# RoomSenosorV1.net
KiCad netlist of a schematic drawn in EAGLE
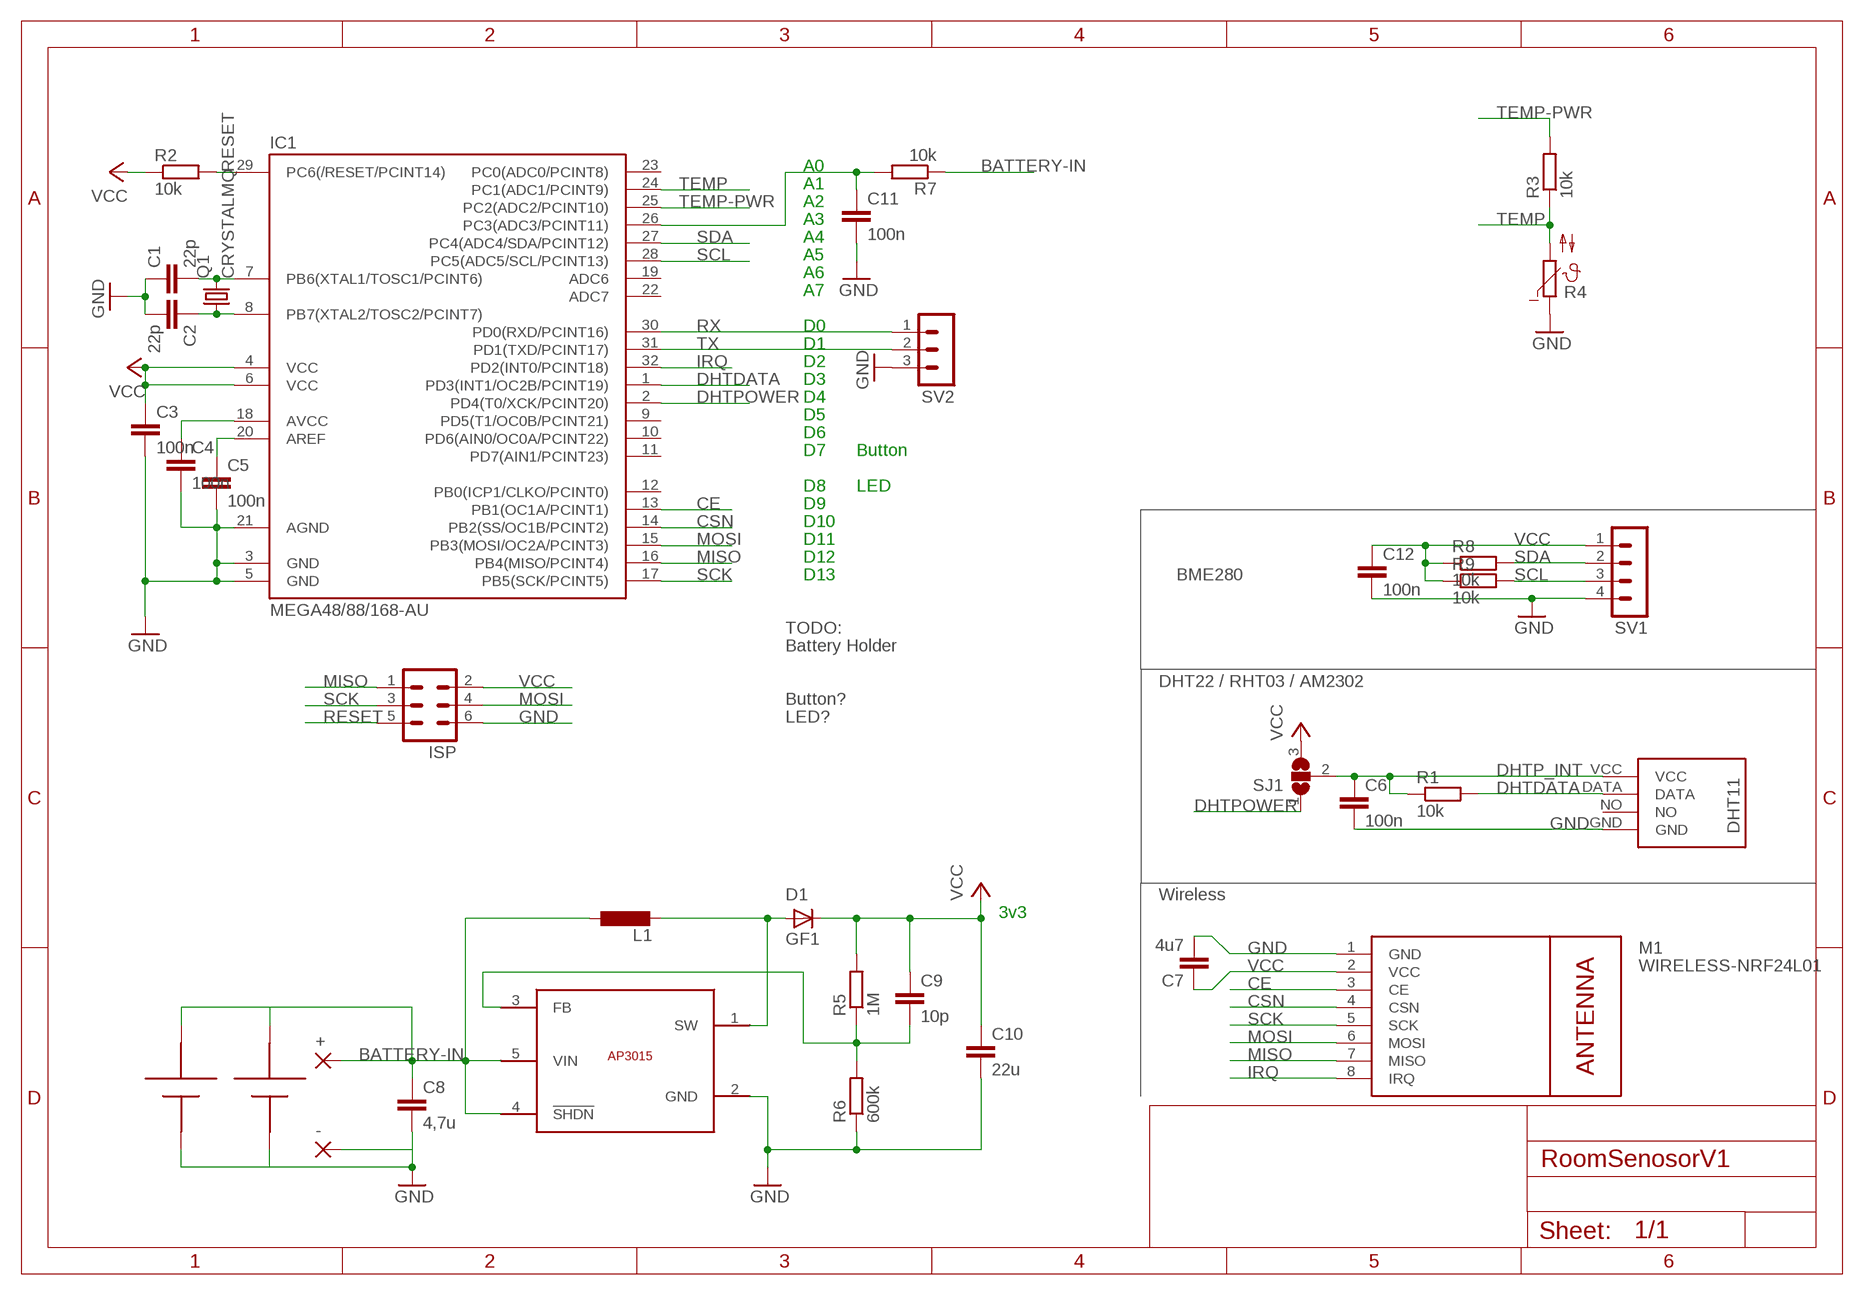
[diagram p0: schematic, sheet 1]

(export (version "E")
  (design (tool "Eeschema 10.0.6"))
  (components
    (comp (ref "+")
      (value "1,6/0,8")
      (footprint "eagle-import:1,6_0,8")
      (libsource (lib "eagle-import") (part "1,6/0,8"))
    )
    (comp (ref "-")
      (value "1,6/0,8")
      (footprint "eagle-import:1,6_0,8")
      (libsource (lib "eagle-import") (part "1,6/0,8"))
    )
    (comp (ref "C1")
      (value "22p")
      (footprint "eagle-import:C0805")
      (libsource (lib "eagle-import") (part "C-EUC0805"))
    )
    (comp (ref "C2")
      (value "22p")
      (footprint "eagle-import:C0805")
      (libsource (lib "eagle-import") (part "C-EUC0805"))
    )
    (comp (ref "C3")
      (value "100n")
      (footprint "eagle-import:C0805")
      (libsource (lib "eagle-import") (part "C-EUC0805"))
    )
    (comp (ref "C4")
      (value "100n")
      (footprint "eagle-import:C0805")
      (libsource (lib "eagle-import") (part "C-EUC0805"))
    )
    (comp (ref "C5")
      (value "100n")
      (footprint "eagle-import:C0805")
      (libsource (lib "eagle-import") (part "C-EUC0805"))
    )
    (comp (ref "C6")
      (value "100n")
      (footprint "eagle-import:C0805")
      (libsource (lib "eagle-import") (part "C-EUC0805"))
    )
    (comp (ref "C7")
      (value "4u7")
      (footprint "eagle-import:C0805")
      (libsource (lib "eagle-import") (part "C-EUC0805"))
    )
    (comp (ref "C8")
      (value "4,7u")
      (footprint "eagle-import:C0805")
      (libsource (lib "eagle-import") (part "C-EUC0805"))
    )
    (comp (ref "C9")
      (value "10p")
      (footprint "eagle-import:C0805")
      (libsource (lib "eagle-import") (part "C-EUC0805"))
    )
    (comp (ref "C10")
      (value "22u")
      (footprint "eagle-import:C1206")
      (libsource (lib "eagle-import") (part "C-EUC1206"))
    )
    (comp (ref "C11")
      (value "100n")
      (footprint "eagle-import:C0805")
      (libsource (lib "eagle-import") (part "C-EUC0805"))
    )
    (comp (ref "C12")
      (value "100n")
      (footprint "eagle-import:C0805")
      (libsource (lib "eagle-import") (part "C-EUC0805"))
    )
    (comp (ref "D1")
      (value "GF1")
      (footprint "eagle-import:SMA-DO214AC")
      (libsource (lib "eagle-import") (part "GF1"))
    )
    (comp (ref "IC1")
      (value "MEGA48/88/168-AU")
      (footprint "eagle-import:TQFP32-08")
      (libsource (lib "eagle-import") (part "MEGA48/88/168-AU"))
    )
    (comp (ref "ISP")
      (value "MA03-2")
      (footprint "eagle-import:MA03-2")
      (libsource (lib "eagle-import") (part "MA03-2"))
    )
    (comp (ref "L1")
      (value "L-EUL2825P")
      (footprint "eagle-import:L2825P")
      (libsource (lib "eagle-import") (part "L-EUL2825P"))
    )
    (comp (ref "M1")
      (value "WIRELESS-NRF24L01")
      (footprint "eagle-import:WIRELESS-NRF24L01")
      (libsource (lib "eagle-import") (part "WIRELESS-NRF24L01"))
    )
    (comp (ref "Q1")
      (value "CRYSTALMQ")
      (footprint "eagle-import:MQ")
      (libsource (lib "eagle-import") (part "CRYSTALMQ"))
    )
    (comp (ref "R1")
      (value "10k")
      (footprint "eagle-import:R0805")
      (libsource (lib "eagle-import") (part "R-EU_R0805"))
    )
    (comp (ref "R2")
      (value "10k")
      (footprint "eagle-import:R0805")
      (libsource (lib "eagle-import") (part "R-EU_R0805"))
    )
    (comp (ref "R3")
      (value "10k")
      (footprint "eagle-import:R0805")
      (libsource (lib "eagle-import") (part "R-EU_R0805"))
    )
    (comp (ref "R4")
      (value "NTC640")
      (footprint "eagle-import:P640")
      (libsource (lib "eagle-import") (part "NTC640"))
    )
    (comp (ref "R5")
      (value "1M")
      (footprint "eagle-import:R0805")
      (libsource (lib "eagle-import") (part "R-EU_R0805"))
    )
    (comp (ref "R6")
      (value "600k")
      (footprint "eagle-import:R0805")
      (libsource (lib "eagle-import") (part "R-EU_R0805"))
    )
    (comp (ref "R7")
      (value "10k")
      (footprint "eagle-import:R0805")
      (libsource (lib "eagle-import") (part "R-EU_R0805"))
    )
    (comp (ref "R8")
      (value "10k")
      (footprint "eagle-import:R0805")
      (libsource (lib "eagle-import") (part "R-EU_R0805"))
    )
    (comp (ref "R9")
      (value "10k")
      (footprint "eagle-import:R0805")
      (libsource (lib "eagle-import") (part "R-EU_R0805"))
    )
    (comp (ref "SJ1")
      (value "SJ2W")
      (footprint "eagle-import:SJ_2")
      (libsource (lib "eagle-import") (part "SJ2W"))
    )
    (comp (ref "SV1")
      (value "MA04-1")
      (footprint "eagle-import:MA04-1")
      (libsource (lib "eagle-import") (part "MA04-1"))
    )
    (comp (ref "SV2")
      (value "MA03-1")
      (footprint "eagle-import:MA03-1")
      (libsource (lib "eagle-import") (part "MA03-1"))
    )
    (comp (ref "U$1")
      (value "AP3015/A")
      (footprint "eagle-import:SOT353")
      (libsource (lib "eagle-import") (part "AP3015/A"))
    )
    (comp (ref "U$2")
      (value "DHT11")
      (footprint "eagle-import:DHT11")
      (libsource (lib "eagle-import") (part "DHT11"))
    )
    (comp (ref "U$3")
      (value "MIGNON_1")
      (footprint "eagle-import:MIGNON_1")
      (libsource (lib "eagle-import") (part "MIGNON_1"))
    )
    (comp (ref "U$4")
      (value "RS_279-4959")
      (footprint "eagle-import:RS_279-4959")
      (libsource (lib "eagle-import") (part "RS_279-4959"))
    )
  )
  (nets
    (net (code "1") (name "/BATTERY-IN") (class "Default")
      (node (ref "+") (pin "1") (pinfunction "P_1") (pintype "passive"))
      (node (ref "C8") (pin "1") (pinfunction "1_1") (pintype "passive"))
      (node (ref "L1") (pin "1") (pinfunction "1_1") (pintype "passive"))
      (node (ref "R7") (pin "1") (pinfunction "1_1") (pintype "passive"))
      (node (ref "U$1") (pin "4") (pinfunction "~{SHDN}_4") (pintype "bidirectional"))
      (node (ref "U$1") (pin "5") (pinfunction "VIN_5") (pintype "bidirectional"))
      (node (ref "U$3") (pin "POS") (pinfunction "POS_POS") (pintype "bidirectional"))
      (node (ref "U$4") (pin "POS") (pinfunction "POS_POS") (pintype "bidirectional"))
    )
    (net (code "2") (name "/CE") (class "Default")
      (node (ref "IC1") (pin "13") (pinfunction "PB1(OC1A/PCINT1)_13") (pintype "bidirectional"))
      (node (ref "M1") (pin "3") (pinfunction "CE_3") (pintype "bidirectional"))
    )
    (net (code "3") (name "/CSN") (class "Default")
      (node (ref "IC1") (pin "14") (pinfunction "PB2(SS/OC1B/PCINT2)_14") (pintype "bidirectional"))
      (node (ref "M1") (pin "4") (pinfunction "CSN_4") (pintype "bidirectional"))
    )
    (net (code "4") (name "/DHTDATA") (class "Default")
      (node (ref "IC1") (pin "1") (pinfunction "PD3(INT1/OC2B/PCINT19)_1") (pintype "bidirectional"))
      (node (ref "R1") (pin "2") (pinfunction "2_2") (pintype "passive"))
      (node (ref "U$2") (pin "DATA") (pinfunction "DATA_DATA") (pintype "bidirectional"))
    )
    (net (code "5") (name "/DHTPOWER") (class "Default")
      (node (ref "IC1") (pin "2") (pinfunction "PD4(T0/XCK/PCINT20)_2") (pintype "bidirectional"))
      (node (ref "SJ1") (pin "1") (pinfunction "1_1") (pintype "passive"))
    )
    (net (code "6") (name "/DHTP_INT") (class "Default")
      (node (ref "C6") (pin "1") (pinfunction "1_1") (pintype "passive"))
      (node (ref "R1") (pin "1") (pinfunction "1_1") (pintype "passive"))
      (node (ref "SJ1") (pin "2") (pinfunction "2_2") (pintype "passive"))
      (node (ref "U$2") (pin "VCC") (pinfunction "VCC_VCC") (pintype "bidirectional"))
    )
    (net (code "7") (name "/IRQ") (class "Default")
      (node (ref "IC1") (pin "32") (pinfunction "PD2(INT0/PCINT18)_32") (pintype "bidirectional"))
      (node (ref "M1") (pin "8") (pinfunction "IRQ_8") (pintype "bidirectional"))
    )
    (net (code "8") (name "/MISO") (class "Default")
      (node (ref "IC1") (pin "16") (pinfunction "PB4(MISO/PCINT4)_16") (pintype "bidirectional"))
      (node (ref "ISP") (pin "1") (pinfunction "1_1") (pintype "passive"))
      (node (ref "M1") (pin "7") (pinfunction "MISO_7") (pintype "bidirectional"))
    )
    (net (code "9") (name "/MOSI") (class "Default")
      (node (ref "IC1") (pin "15") (pinfunction "PB3(MOSI/OC2A/PCINT3)_15") (pintype "bidirectional"))
      (node (ref "ISP") (pin "4") (pinfunction "4_4") (pintype "passive"))
      (node (ref "M1") (pin "6") (pinfunction "MOSI_6") (pintype "bidirectional"))
    )
    (net (code "10") (name "/RESET") (class "Default")
      (node (ref "IC1") (pin "29") (pinfunction "PC6(/RESET/PCINT14)_29") (pintype "bidirectional"))
      (node (ref "ISP") (pin "5") (pinfunction "5_5") (pintype "passive"))
      (node (ref "R2") (pin "2") (pinfunction "2_2") (pintype "passive"))
    )
    (net (code "11") (name "/RX") (class "Default")
      (node (ref "IC1") (pin "30") (pinfunction "PD0(RXD/PCINT16)_30") (pintype "bidirectional"))
      (node (ref "SV2") (pin "1") (pinfunction "1_1") (pintype "passive"))
    )
    (net (code "12") (name "/SCK") (class "Default")
      (node (ref "IC1") (pin "17") (pinfunction "PB5(SCK/PCINT5)_17") (pintype "bidirectional"))
      (node (ref "ISP") (pin "3") (pinfunction "3_3") (pintype "passive"))
      (node (ref "M1") (pin "5") (pinfunction "SCK_5") (pintype "bidirectional"))
    )
    (net (code "13") (name "/SCL") (class "Default")
      (node (ref "IC1") (pin "28") (pinfunction "PC5(ADC5/SCL/PCINT13)_28") (pintype "bidirectional"))
      (node (ref "R9") (pin "2") (pinfunction "2_2") (pintype "passive"))
      (node (ref "SV1") (pin "3") (pinfunction "3_3") (pintype "passive"))
    )
    (net (code "14") (name "/SDA") (class "Default")
      (node (ref "IC1") (pin "27") (pinfunction "PC4(ADC4/SDA/PCINT12)_27") (pintype "bidirectional"))
      (node (ref "R8") (pin "2") (pinfunction "2_2") (pintype "passive"))
      (node (ref "SV1") (pin "2") (pinfunction "2_2") (pintype "passive"))
    )
    (net (code "15") (name "/TEMP") (class "Default")
      (node (ref "IC1") (pin "24") (pinfunction "PC1(ADC1/PCINT9)_24") (pintype "bidirectional"))
      (node (ref "R3") (pin "1") (pinfunction "1_1") (pintype "passive"))
      (node (ref "R4") (pin "2") (pinfunction "2_2") (pintype "passive"))
    )
    (net (code "16") (name "/TEMP-PWR") (class "Default")
      (node (ref "IC1") (pin "25") (pinfunction "PC2(ADC2/PCINT10)_25") (pintype "bidirectional"))
      (node (ref "R3") (pin "2") (pinfunction "2_2") (pintype "passive"))
    )
    (net (code "17") (name "/TX") (class "Default")
      (node (ref "IC1") (pin "31") (pinfunction "PD1(TXD/PCINT17)_31") (pintype "bidirectional"))
      (node (ref "SV2") (pin "2") (pinfunction "2_2") (pintype "passive"))
    )
    (net (code "18") (name "GND") (class "Default")
      (node (ref "-") (pin "1") (pinfunction "P_1") (pintype "passive"))
      (node (ref "C1") (pin "1") (pinfunction "1_1") (pintype "passive"))
      (node (ref "C10") (pin "2") (pinfunction "2_2") (pintype "passive"))
      (node (ref "C11") (pin "2") (pinfunction "2_2") (pintype "passive"))
      (node (ref "C12") (pin "2") (pinfunction "2_2") (pintype "passive"))
      (node (ref "C2") (pin "2") (pinfunction "2_2") (pintype "passive"))
      (node (ref "C3") (pin "2") (pinfunction "2_2") (pintype "passive"))
      (node (ref "C4") (pin "2") (pinfunction "2_2") (pintype "passive"))
      (node (ref "C5") (pin "2") (pinfunction "2_2") (pintype "passive"))
      (node (ref "C6") (pin "2") (pinfunction "2_2") (pintype "passive"))
      (node (ref "C7") (pin "2") (pinfunction "2_2") (pintype "passive"))
      (node (ref "C8") (pin "2") (pinfunction "2_2") (pintype "passive"))
      (node (ref "IC1") (pin "21") (pinfunction "AGND_21") (pintype "power_in"))
      (node (ref "IC1") (pin "3") (pinfunction "GND_3") (pintype "power_in"))
      (node (ref "IC1") (pin "5") (pinfunction "GND_5") (pintype "power_in"))
      (node (ref "ISP") (pin "6") (pinfunction "6_6") (pintype "passive"))
      (node (ref "M1") (pin "1") (pinfunction "GND_1") (pintype "power_in"))
      (node (ref "R4") (pin "1") (pinfunction "1_1") (pintype "passive"))
      (node (ref "R6") (pin "1") (pinfunction "1_1") (pintype "passive"))
      (node (ref "SV1") (pin "4") (pinfunction "4_4") (pintype "passive"))
      (node (ref "SV2") (pin "3") (pinfunction "3_3") (pintype "passive"))
      (node (ref "U$1") (pin "2") (pinfunction "GND_2") (pintype "bidirectional"))
      (node (ref "U$2") (pin "GND") (pinfunction "GND_GND") (pintype "bidirectional"))
      (node (ref "U$3") (pin "NEG") (pinfunction "NEG_NEG") (pintype "bidirectional"))
      (node (ref "U$4") (pin "NEG") (pinfunction "NEG_NEG") (pintype "bidirectional"))
    )
    (net (code "19") (name "Net-(IC1-AREF)") (class "Default")
      (node (ref "C5") (pin "1") (pinfunction "1_1") (pintype "passive"))
      (node (ref "IC1") (pin "20") (pinfunction "AREF_20") (pintype "passive"))
    )
    (net (code "20") (name "Net-(IC1-AVCC)") (class "Default")
      (node (ref "C4") (pin "1") (pinfunction "1_1") (pintype "passive"))
      (node (ref "IC1") (pin "18") (pinfunction "AVCC_18") (pintype "passive"))
    )
    (net (code "21") (name "Net-(IC1-PB6(XTAL1{slash}TOSC1{slash}PCINT6))") (class "Default")
      (node (ref "C1") (pin "2") (pinfunction "2_2") (pintype "passive"))
      (node (ref "IC1") (pin "7") (pinfunction "PB6(XTAL1/TOSC1/PCINT6)_7") (pintype "bidirectional"))
      (node (ref "Q1") (pin "P3") (pinfunction "2_P3") (pintype "passive"))
    )
    (net (code "22") (name "Net-(IC1-PB7(XTAL2{slash}TOSC2{slash}PCINT7))") (class "Default")
      (node (ref "C2") (pin "1") (pinfunction "1_1") (pintype "passive"))
      (node (ref "IC1") (pin "8") (pinfunction "PB7(XTAL2/TOSC2/PCINT7)_8") (pintype "bidirectional"))
      (node (ref "Q1") (pin "P1") (pinfunction "1_P1") (pintype "passive"))
    )
    (net (code "23") (name "Net-(IC1-PC3(ADC3{slash}PCINT11))") (class "Default")
      (node (ref "C11") (pin "1") (pinfunction "1_1") (pintype "passive"))
      (node (ref "IC1") (pin "26") (pinfunction "PC3(ADC3/PCINT11)_26") (pintype "bidirectional"))
      (node (ref "R7") (pin "2") (pinfunction "2_2") (pintype "passive"))
    )
    (net (code "24") (name "Net-(U$1-FB)") (class "Default")
      (node (ref "C9") (pin "2") (pinfunction "2_2") (pintype "passive"))
      (node (ref "R5") (pin "1") (pinfunction "1_1") (pintype "passive"))
      (node (ref "R6") (pin "2") (pinfunction "2_2") (pintype "passive"))
      (node (ref "U$1") (pin "3") (pinfunction "FB_3") (pintype "bidirectional"))
    )
    (net (code "25") (name "Net-(U$1-SW)") (class "Default")
      (node (ref "D1") (pin "A") (pinfunction "A_A") (pintype "passive"))
      (node (ref "L1") (pin "2") (pinfunction "2_2") (pintype "passive"))
      (node (ref "U$1") (pin "1") (pinfunction "SW_1") (pintype "bidirectional"))
    )
    (net (code "26") (name "VCC") (class "Default")
      (node (ref "C10") (pin "1") (pinfunction "1_1") (pintype "passive"))
      (node (ref "C12") (pin "1") (pinfunction "1_1") (pintype "passive"))
      (node (ref "C3") (pin "1") (pinfunction "1_1") (pintype "passive"))
      (node (ref "C7") (pin "1") (pinfunction "1_1") (pintype "passive"))
      (node (ref "C9") (pin "1") (pinfunction "1_1") (pintype "passive"))
      (node (ref "D1") (pin "K") (pinfunction "C_K") (pintype "passive"))
      (node (ref "IC1") (pin "4") (pinfunction "VCC_4") (pintype "power_in"))
      (node (ref "IC1") (pin "6") (pinfunction "VCC_6") (pintype "power_in"))
      (node (ref "ISP") (pin "2") (pinfunction "2_2") (pintype "passive"))
      (node (ref "M1") (pin "2") (pinfunction "VCC_2") (pintype "power_in"))
      (node (ref "R2") (pin "1") (pinfunction "1_1") (pintype "passive"))
      (node (ref "R5") (pin "2") (pinfunction "2_2") (pintype "passive"))
      (node (ref "R8") (pin "1") (pinfunction "1_1") (pintype "passive"))
      (node (ref "R9") (pin "1") (pinfunction "1_1") (pintype "passive"))
      (node (ref "SJ1") (pin "3") (pinfunction "3_3") (pintype "passive"))
      (node (ref "SV1") (pin "1") (pinfunction "1_1") (pintype "passive"))
    )
    (net (code "27") (name "unconnected-(IC1-ADC6-Pad19)") (class "Default")
      (node (ref "IC1") (pin "19") (pinfunction "ADC6_19") (pintype "passive"))
    )
    (net (code "28") (name "unconnected-(IC1-ADC7-Pad22)") (class "Default")
      (node (ref "IC1") (pin "22") (pinfunction "ADC7_22") (pintype "passive"))
    )
    (net (code "29") (name "unconnected-(IC1-PB0(ICP1{slash}CLKO{slash}PCINT0)-Pad12)") (class "Default")
      (node (ref "IC1") (pin "12") (pinfunction "PB0(ICP1/CLKO/PCINT0)_12") (pintype "bidirectional"))
    )
    (net (code "30") (name "unconnected-(IC1-PC0(ADC0{slash}PCINT8)-Pad23)") (class "Default")
      (node (ref "IC1") (pin "23") (pinfunction "PC0(ADC0/PCINT8)_23") (pintype "bidirectional"))
    )
    (net (code "31") (name "unconnected-(IC1-PD5(T1{slash}OC0B{slash}PCINT21)-Pad9)") (class "Default")
      (node (ref "IC1") (pin "9") (pinfunction "PD5(T1/OC0B/PCINT21)_9") (pintype "bidirectional"))
    )
    (net (code "32") (name "unconnected-(IC1-PD6(AIN0{slash}OC0A{slash}PCINT22)-Pad10)") (class "Default")
      (node (ref "IC1") (pin "10") (pinfunction "PD6(AIN0/OC0A/PCINT22)_10") (pintype "bidirectional"))
    )
    (net (code "33") (name "unconnected-(IC1-PD7(AIN1{slash}PCINT23)-Pad11)") (class "Default")
      (node (ref "IC1") (pin "11") (pinfunction "PD7(AIN1/PCINT23)_11") (pintype "bidirectional"))
    )
    (net (code "34") (name "unconnected-(U$2-PadNO)") (class "Default")
      (node (ref "U$2") (pin "NO") (pinfunction "NO_NO") (pintype "bidirectional"))
    )
  )
)
